# design.net
KiCad netlist of a schematic drawn in Altium Designer
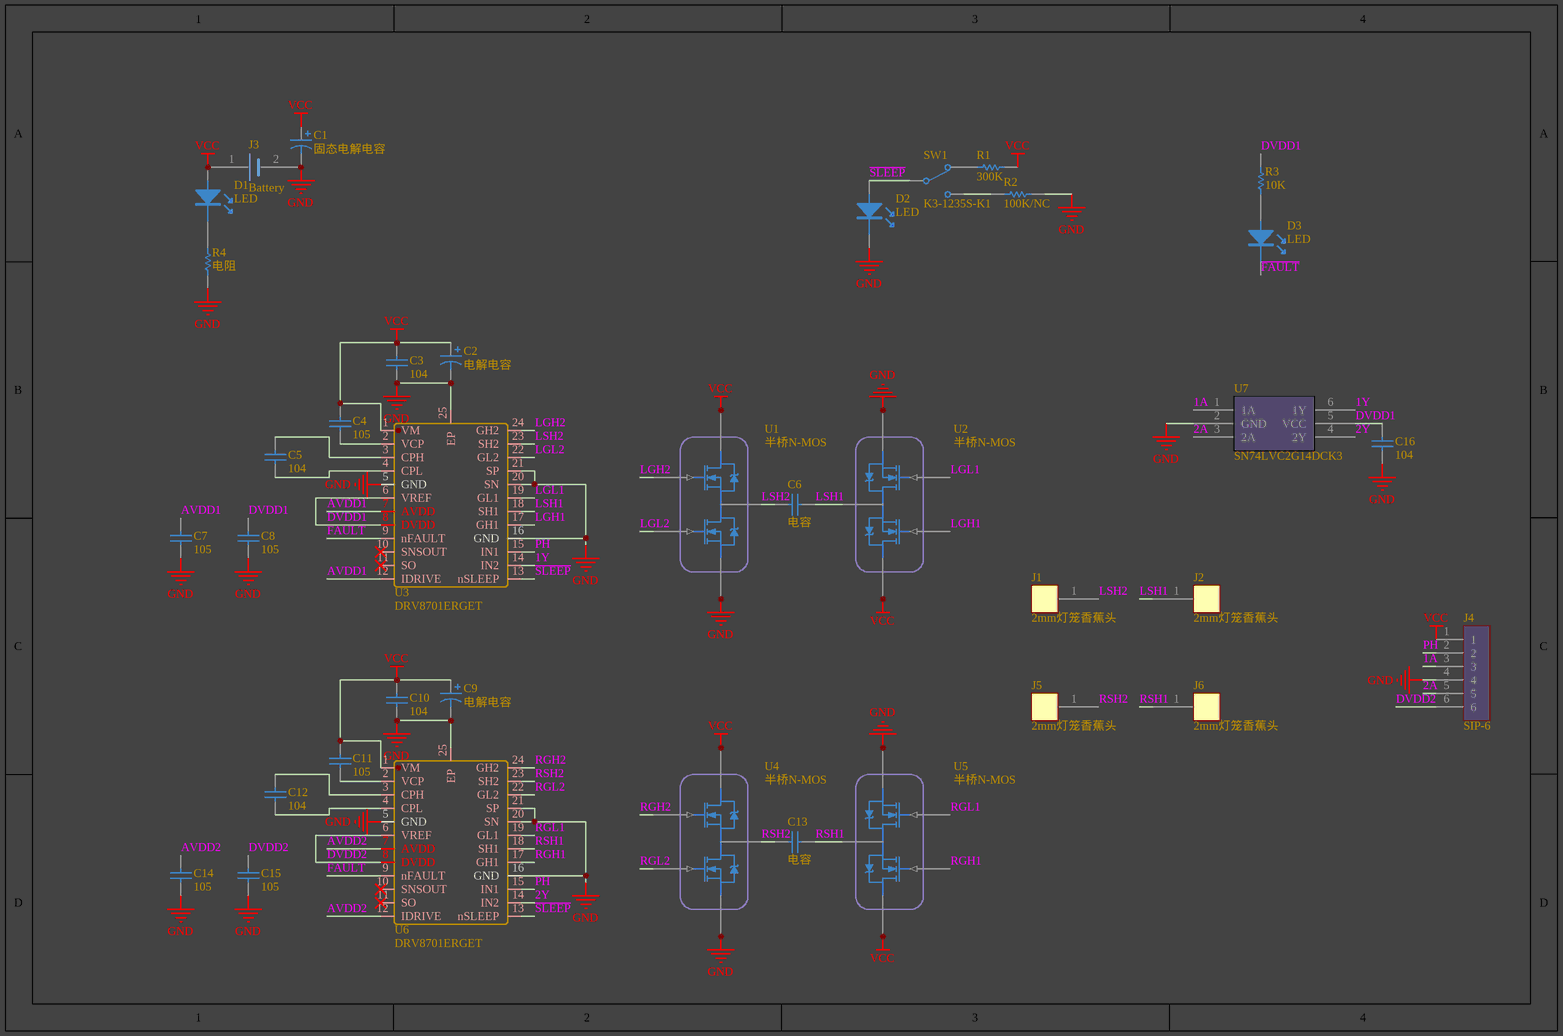
[diagram p0: 原理图.SchDoc]

(export (version "E")
  (design (tool "Eeschema 10.0.6"))
  (components
    (comp (ref "C1")
      (value "固态电解电容")
      (footprint "贴片电解 10*10.5")
      (description "Polarized Capacitor (Axial)")
      (fields (field (name "PUBLISHER") "Altium Limited"))
      (libsource (lib "iMag") (part "电解电容"))
    )
    (comp (ref "C2")
      (value "电解电容")
      (footprint "贴片电解 4*5.4")
      (description "Polarized Capacitor (Axial)")
      (fields (field (name "PUBLISHER") "Altium Limited"))
      (libsource (lib "iMag") (part "电解电容"))
    )
    (comp (ref "C3")
      (value "104")
      (footprint "C0402")
      (description "Capacitor")
      (fields (field (name "PUBLISHER") "Altium Limited"))
      (libsource (lib "iMag") (part "电容"))
    )
    (comp (ref "C4")
      (value "105")
      (footprint "C0402")
      (description "Capacitor")
      (fields (field (name "PUBLISHER") "Altium Limited"))
      (libsource (lib "iMag") (part "电容"))
    )
    (comp (ref "C5")
      (value "104")
      (footprint "C0402")
      (description "Capacitor")
      (fields (field (name "PUBLISHER") "Altium Limited"))
      (libsource (lib "iMag") (part "电容"))
    )
    (comp (ref "C6")
      (value "电容")
      (footprint "C0603")
      (description "Capacitor")
      (fields (field (name "PUBLISHER") "Altium Limited"))
      (libsource (lib "iMag") (part "电容"))
    )
    (comp (ref "C7")
      (value "105")
      (footprint "C0402")
      (description "Capacitor")
      (fields (field (name "PUBLISHER") "Altium Limited"))
      (libsource (lib "iMag") (part "电容"))
    )
    (comp (ref "C8")
      (value "105")
      (footprint "C0402")
      (description "Capacitor")
      (fields (field (name "PUBLISHER") "Altium Limited"))
      (libsource (lib "iMag") (part "电容"))
    )
    (comp (ref "C9")
      (value "电解电容")
      (footprint "贴片电解 4*5.4")
      (description "Polarized Capacitor (Axial)")
      (fields (field (name "PUBLISHER") "Altium Limited"))
      (libsource (lib "iMag") (part "电解电容"))
    )
    (comp (ref "C10")
      (value "104")
      (footprint "C0402")
      (description "Capacitor")
      (fields (field (name "PUBLISHER") "Altium Limited"))
      (libsource (lib "iMag") (part "电容"))
    )
    (comp (ref "C11")
      (value "105")
      (footprint "C0402")
      (description "Capacitor")
      (fields (field (name "PUBLISHER") "Altium Limited"))
      (libsource (lib "iMag") (part "电容"))
    )
    (comp (ref "C12")
      (value "104")
      (footprint "C0402")
      (description "Capacitor")
      (fields (field (name "PUBLISHER") "Altium Limited"))
      (libsource (lib "iMag") (part "电容"))
    )
    (comp (ref "C13")
      (value "电容")
      (footprint "C0603")
      (description "Capacitor")
      (fields (field (name "PUBLISHER") "Altium Limited"))
      (libsource (lib "iMag") (part "电容"))
    )
    (comp (ref "C14")
      (value "105")
      (footprint "C0402")
      (description "Capacitor")
      (fields (field (name "PUBLISHER") "Altium Limited"))
      (libsource (lib "iMag") (part "电容"))
    )
    (comp (ref "C15")
      (value "105")
      (footprint "C0402")
      (description "Capacitor")
      (fields (field (name "PUBLISHER") "Altium Limited"))
      (libsource (lib "iMag") (part "电容"))
    )
    (comp (ref "C16")
      (value "104")
      (footprint "C0402")
      (description "Capacitor")
      (fields (field (name "PUBLISHER") "Altium Limited"))
      (libsource (lib "iMag") (part "电容"))
    )
    (comp (ref "D1") (value "LED") (footprint "LED 0603B") (libsource (lib "iMag") (part "LED")))
    (comp (ref "D2") (value "LED") (footprint "LED 0603G") (libsource (lib "iMag") (part "LED")))
    (comp (ref "D3") (value "LED") (footprint "LED 0603R") (libsource (lib "iMag") (part "LED")))
    (comp (ref "J1") (value "2mm灯笼香蕉头") (footprint "MOTOR") (libsource (lib "") (part "2mm灯笼香蕉头_1")))
    (comp (ref "J2") (value "2mm灯笼香蕉头") (footprint "MOTOR") (libsource (lib "iMag") (part "2mm灯笼香蕉头")))
    (comp (ref "J3") (value "Battery") (footprint "T插") (libsource (lib "iMag") (part "Battery")))
    (comp (ref "J4") (value "SIP-6") (footprint "PH2.0-6P") (libsource (lib "iMag") (part "SIP-6")))
    (comp (ref "J5") (value "2mm灯笼香蕉头") (footprint "MOTOR") (libsource (lib "") (part "2mm灯笼香蕉头_1")))
    (comp (ref "J6") (value "2mm灯笼香蕉头") (footprint "MOTOR") (libsource (lib "iMag") (part "2mm灯笼香蕉头")))
    (comp (ref "R1")
      (value "300K")
      (footprint "R0402")
      (description "Resistor")
      (fields (field (name "PUBLISHER") "Altium Limited"))
      (libsource (lib "iMag") (part "电阻"))
    )
    (comp (ref "R2")
      (value "100K/NC")
      (footprint "R0402")
      (description "Resistor")
      (fields (field (name "PUBLISHER") "Altium Limited"))
      (libsource (lib "iMag") (part "电阻"))
    )
    (comp (ref "R3")
      (value "10K")
      (footprint "R0402")
      (description "Resistor")
      (fields (field (name "PUBLISHER") "Altium Limited"))
      (libsource (lib "iMag") (part "电阻"))
    )
    (comp (ref "R4")
      (value "电阻")
      (footprint "R0402")
      (description "Resistor")
      (fields (field (name "PUBLISHER") "Altium Limited"))
      (libsource (lib "iMag") (part "电阻"))
    )
    (comp (ref "SW1")
      (value "K3-1235S-K1")
      (footprint "K3-1235S-K1")
      (description "Switch")
      (libsource (lib "iMag") (part "单刀双掷"))
    )
    (comp (ref "U1") (value "半桥N-MOS") (footprint "VDFN8") (libsource (lib "iMag") (part "半桥N-MOS")))
    (comp (ref "U2") (value "半桥N-MOS") (footprint "VDFN8") (libsource (lib "iMag") (part "半桥N-MOS")))
    (comp (ref "U3")
      (value "DRV8701ERGET")
      (footprint "VQFN-24_24PIN-L4.00-W4.00-PITCH0.50-EP-TL")
      (description "H桥驱动")
      (fields (field (name "BOM_SUPPLIER PART") "C132049") (field (name "CONTRIBUTOR") "LCSC"))
      (libsource (lib "iMag") (part "DRV8701"))
    )
    (comp (ref "U4") (value "半桥N-MOS") (footprint "VDFN8") (libsource (lib "iMag") (part "半桥N-MOS")))
    (comp (ref "U5") (value "半桥N-MOS") (footprint "VDFN8") (libsource (lib "iMag") (part "半桥N-MOS")))
    (comp (ref "U6")
      (value "DRV8701ERGET")
      (footprint "VQFN-24_24PIN-L4.00-W4.00-PITCH0.50-EP-TL")
      (description "H桥驱动")
      (fields (field (name "BOM_SUPPLIER PART") "C132049") (field (name "CONTRIBUTOR") "LCSC"))
      (libsource (lib "iMag") (part "DRV8701"))
    )
    (comp (ref "U7")
      (value "SN74LVC2G14DCK3")
      (footprint "SC70")
      (description "门级和反向器")
      (fields (field (name "COPYRIGHT") "Copyright (C) 2018 Accelerated Designs. All rights reserved"))
      (libsource (lib "iMag") (part "SN74LVC2G14DCK3"))
    )
  )
  (nets
    (net (code "1") (name "/1A") (class "Default")
      (node (ref "J4") (pin "3") (pinfunction "3_3") (pintype "passive"))
      (node (ref "U7") (pin "1") (pinfunction "1A_1") (pintype "passive"))
    )
    (net (code "2") (name "/1Y") (class "Default")
      (node (ref "U3") (pin "14") (pinfunction "IN2_14") (pintype "passive"))
      (node (ref "U7") (pin "6") (pinfunction "1Y_6") (pintype "passive"))
    )
    (net (code "3") (name "/2A") (class "Default")
      (node (ref "J4") (pin "5") (pinfunction "5_5") (pintype "passive"))
      (node (ref "U7") (pin "3") (pinfunction "2A_3") (pintype "passive"))
    )
    (net (code "4") (name "/2Y") (class "Default")
      (node (ref "U6") (pin "14") (pinfunction "IN2_14") (pintype "passive"))
      (node (ref "U7") (pin "4") (pinfunction "2Y_4") (pintype "passive"))
    )
    (net (code "5") (name "/AVDD1") (class "Default")
      (node (ref "C7") (pin "2") (pinfunction "2_2") (pintype "passive"))
      (node (ref "U3") (pin "12") (pinfunction "IDRIVE_12") (pintype "passive"))
      (node (ref "U3") (pin "7") (pinfunction "AVDD_7") (pintype "passive"))
    )
    (net (code "6") (name "/AVDD2") (class "Default")
      (node (ref "C14") (pin "2") (pinfunction "2_2") (pintype "passive"))
      (node (ref "U6") (pin "12") (pinfunction "IDRIVE_12") (pintype "passive"))
      (node (ref "U6") (pin "7") (pinfunction "AVDD_7") (pintype "passive"))
    )
    (net (code "7") (name "/DVDD1") (class "Default")
      (node (ref "C16") (pin "2") (pinfunction "2_2") (pintype "passive"))
      (node (ref "C8") (pin "2") (pinfunction "2_2") (pintype "passive"))
      (node (ref "R3") (pin "1") (pinfunction "1_1") (pintype "passive"))
      (node (ref "U3") (pin "6") (pinfunction "VREF_6") (pintype "passive"))
      (node (ref "U3") (pin "8") (pinfunction "DVDD_8") (pintype "passive"))
      (node (ref "U7") (pin "5") (pinfunction "VCC_5") (pintype "passive"))
    )
    (net (code "8") (name "/DVDD2") (class "Default")
      (node (ref "C15") (pin "2") (pinfunction "2_2") (pintype "passive"))
      (node (ref "J4") (pin "6") (pinfunction "6_6") (pintype "passive"))
      (node (ref "U6") (pin "6") (pinfunction "VREF_6") (pintype "passive"))
      (node (ref "U6") (pin "8") (pinfunction "DVDD_8") (pintype "passive"))
    )
    (net (code "9") (name "/FAULT") (class "Default")
      (node (ref "D3") (pin "K") (pinfunction "2_K") (pintype "passive"))
      (node (ref "U3") (pin "9") (pinfunction "nFAULT_9") (pintype "passive"))
      (node (ref "U6") (pin "9") (pinfunction "nFAULT_9") (pintype "passive"))
    )
    (net (code "10") (name "/LGH1") (class "Default")
      (node (ref "U2") (pin "1") (pinfunction "GH_1") (pintype "input"))
      (node (ref "U3") (pin "17") (pinfunction "GH1_17") (pintype "passive"))
    )
    (net (code "11") (name "/LGH2") (class "Default")
      (node (ref "U1") (pin "1") (pinfunction "GH_1") (pintype "input"))
      (node (ref "U3") (pin "24") (pinfunction "GH2_24") (pintype "passive"))
    )
    (net (code "12") (name "/LGL1") (class "Default")
      (node (ref "U2") (pin "8") (pinfunction "GL_8") (pintype "input"))
      (node (ref "U3") (pin "19") (pinfunction "GL1_19") (pintype "passive"))
    )
    (net (code "13") (name "/LGL2") (class "Default")
      (node (ref "U1") (pin "8") (pinfunction "GL_8") (pintype "input"))
      (node (ref "U3") (pin "22") (pinfunction "GL2_22") (pintype "passive"))
    )
    (net (code "14") (name "/LSH1") (class "Default")
      (node (ref "C6") (pin "2") (pinfunction "2_2") (pintype "passive"))
      (node (ref "J2") (pin "1") (pinfunction "0_1") (pintype "passive"))
      (node (ref "U2") (pin "9") (pinfunction "9_9") (pintype "passive"))
      (node (ref "U3") (pin "18") (pinfunction "SH1_18") (pintype "passive"))
    )
    (net (code "15") (name "/LSH2") (class "Default")
      (node (ref "C6") (pin "1") (pinfunction "1_1") (pintype "passive"))
      (node (ref "J1") (pin "1") (pinfunction "0_1") (pintype "passive"))
      (node (ref "U1") (pin "9") (pinfunction "9_9") (pintype "passive"))
      (node (ref "U3") (pin "23") (pinfunction "SH2_23") (pintype "passive"))
    )
    (net (code "16") (name "/PH") (class "Default")
      (node (ref "J4") (pin "2") (pinfunction "2_2") (pintype "passive"))
      (node (ref "U3") (pin "15") (pinfunction "IN1_15") (pintype "passive"))
      (node (ref "U6") (pin "15") (pinfunction "IN1_15") (pintype "passive"))
    )
    (net (code "17") (name "/RGH1") (class "Default")
      (node (ref "U5") (pin "1") (pinfunction "GH_1") (pintype "input"))
      (node (ref "U6") (pin "17") (pinfunction "GH1_17") (pintype "passive"))
    )
    (net (code "18") (name "/RGH2") (class "Default")
      (node (ref "U4") (pin "1") (pinfunction "GH_1") (pintype "input"))
      (node (ref "U6") (pin "24") (pinfunction "GH2_24") (pintype "passive"))
    )
    (net (code "19") (name "/RGL1") (class "Default")
      (node (ref "U5") (pin "8") (pinfunction "GL_8") (pintype "input"))
      (node (ref "U6") (pin "19") (pinfunction "GL1_19") (pintype "passive"))
    )
    (net (code "20") (name "/RGL2") (class "Default")
      (node (ref "U4") (pin "8") (pinfunction "GL_8") (pintype "input"))
      (node (ref "U6") (pin "22") (pinfunction "GL2_22") (pintype "passive"))
    )
    (net (code "21") (name "/RSH1") (class "Default")
      (node (ref "C13") (pin "2") (pinfunction "2_2") (pintype "passive"))
      (node (ref "J6") (pin "1") (pinfunction "0_1") (pintype "passive"))
      (node (ref "U5") (pin "9") (pinfunction "9_9") (pintype "passive"))
      (node (ref "U6") (pin "18") (pinfunction "SH1_18") (pintype "passive"))
    )
    (net (code "22") (name "/RSH2") (class "Default")
      (node (ref "C13") (pin "1") (pinfunction "1_1") (pintype "passive"))
      (node (ref "J5") (pin "1") (pinfunction "0_1") (pintype "passive"))
      (node (ref "U4") (pin "9") (pinfunction "9_9") (pintype "passive"))
      (node (ref "U6") (pin "23") (pinfunction "SH2_23") (pintype "passive"))
    )
    (net (code "23") (name "/SLEEP") (class "Default")
      (node (ref "D2") (pin "A") (pinfunction "1_A") (pintype "passive"))
      (node (ref "SW1") (pin "2") (pinfunction "2_2") (pintype "passive"))
      (node (ref "U3") (pin "13") (pinfunction "nSLEEP_13") (pintype "passive"))
      (node (ref "U6") (pin "13") (pinfunction "nSLEEP_13") (pintype "passive"))
    )
    (net (code "24") (name "GND") (class "Default")
      (node (ref "C1") (pin "2") (pinfunction "2_2") (pintype "passive"))
      (node (ref "C10") (pin "1") (pinfunction "1_1") (pintype "passive"))
      (node (ref "C14") (pin "1") (pinfunction "1_1") (pintype "passive"))
      (node (ref "C15") (pin "1") (pinfunction "1_1") (pintype "passive"))
      (node (ref "C16") (pin "1") (pinfunction "1_1") (pintype "passive"))
      (node (ref "C2") (pin "2") (pinfunction "2_2") (pintype "passive"))
      (node (ref "C3") (pin "1") (pinfunction "1_1") (pintype "passive"))
      (node (ref "C7") (pin "1") (pinfunction "1_1") (pintype "passive"))
      (node (ref "C8") (pin "1") (pinfunction "1_1") (pintype "passive"))
      (node (ref "C9") (pin "2") (pinfunction "2_2") (pintype "passive"))
      (node (ref "D2") (pin "K") (pinfunction "2_K") (pintype "passive"))
      (node (ref "J3") (pin "2") (pinfunction "-_2") (pintype "passive"))
      (node (ref "J4") (pin "4") (pinfunction "4_4") (pintype "passive"))
      (node (ref "R2") (pin "1") (pinfunction "1_1") (pintype "passive"))
      (node (ref "R4") (pin "1") (pinfunction "1_1") (pintype "passive"))
      (node (ref "U1") (pin "5") (pinfunction "SL_5") (pintype "passive"))
      (node (ref "U1") (pin "6") (pinfunction "SL_6") (pintype "passive"))
      (node (ref "U1") (pin "7") (pinfunction "S_7") (pintype "passive"))
      (node (ref "U2") (pin "5") (pinfunction "SL_5") (pintype "passive"))
      (node (ref "U2") (pin "6") (pinfunction "SL_6") (pintype "passive"))
      (node (ref "U2") (pin "7") (pinfunction "S_7") (pintype "passive"))
      (node (ref "U3") (pin "16") (pinfunction "GND_16") (pintype "passive"))
      (node (ref "U3") (pin "20") (pinfunction "SN_20") (pintype "passive"))
      (node (ref "U3") (pin "21") (pinfunction "SP_21") (pintype "passive"))
      (node (ref "U3") (pin "25") (pinfunction "EP_25") (pintype "passive"))
      (node (ref "U3") (pin "5") (pinfunction "GND_5") (pintype "passive"))
      (node (ref "U4") (pin "5") (pinfunction "SL_5") (pintype "passive"))
      (node (ref "U4") (pin "6") (pinfunction "SL_6") (pintype "passive"))
      (node (ref "U4") (pin "7") (pinfunction "S_7") (pintype "passive"))
      (node (ref "U5") (pin "5") (pinfunction "SL_5") (pintype "passive"))
      (node (ref "U5") (pin "6") (pinfunction "SL_6") (pintype "passive"))
      (node (ref "U5") (pin "7") (pinfunction "S_7") (pintype "passive"))
      (node (ref "U6") (pin "16") (pinfunction "GND_16") (pintype "passive"))
      (node (ref "U6") (pin "20") (pinfunction "SN_20") (pintype "passive"))
      (node (ref "U6") (pin "21") (pinfunction "SP_21") (pintype "passive"))
      (node (ref "U6") (pin "25") (pinfunction "EP_25") (pintype "passive"))
      (node (ref "U6") (pin "5") (pinfunction "GND_5") (pintype "passive"))
      (node (ref "U7") (pin "2") (pinfunction "GND_2") (pintype "passive"))
    )
    (net (code "25") (name "Net-(D1-2)") (class "Default")
      (node (ref "D1") (pin "K") (pinfunction "2_K") (pintype "passive"))
      (node (ref "R4") (pin "2") (pinfunction "2_2") (pintype "passive"))
    )
    (net (code "26") (name "Net-(D3-1)") (class "Default")
      (node (ref "D3") (pin "A") (pinfunction "1_A") (pintype "passive"))
      (node (ref "R3") (pin "2") (pinfunction "2_2") (pintype "passive"))
    )
    (net (code "27") (name "Net-(R1-Pad2)") (class "Default")
      (node (ref "R1") (pin "2") (pinfunction "2_2") (pintype "passive"))
      (node (ref "SW1") (pin "1") (pinfunction "1_1") (pintype "passive"))
    )
    (net (code "28") (name "Net-(R2-Pad2)") (class "Default")
      (node (ref "R2") (pin "2") (pinfunction "2_2") (pintype "passive"))
      (node (ref "SW1") (pin "3") (pinfunction "3_3") (pintype "passive"))
    )
    (net (code "29") (name "Net-(U3-CPH)") (class "Default")
      (node (ref "C5") (pin "2") (pinfunction "2_2") (pintype "passive"))
      (node (ref "U3") (pin "3") (pinfunction "CPH_3") (pintype "passive"))
    )
    (net (code "30") (name "Net-(U3-CPL)") (class "Default")
      (node (ref "C5") (pin "1") (pinfunction "1_1") (pintype "passive"))
      (node (ref "U3") (pin "4") (pinfunction "CPL_4") (pintype "passive"))
    )
    (net (code "31") (name "Net-(U3-VCP)") (class "Default")
      (node (ref "C4") (pin "1") (pinfunction "1_1") (pintype "passive"))
      (node (ref "U3") (pin "2") (pinfunction "VCP_2") (pintype "passive"))
    )
    (net (code "32") (name "Net-(U6-CPH)") (class "Default")
      (node (ref "C12") (pin "2") (pinfunction "2_2") (pintype "passive"))
      (node (ref "U6") (pin "3") (pinfunction "CPH_3") (pintype "passive"))
    )
    (net (code "33") (name "Net-(U6-CPL)") (class "Default")
      (node (ref "C12") (pin "1") (pinfunction "1_1") (pintype "passive"))
      (node (ref "U6") (pin "4") (pinfunction "CPL_4") (pintype "passive"))
    )
    (net (code "34") (name "Net-(U6-VCP)") (class "Default")
      (node (ref "C11") (pin "1") (pinfunction "1_1") (pintype "passive"))
      (node (ref "U6") (pin "2") (pinfunction "VCP_2") (pintype "passive"))
    )
    (net (code "35") (name "VCC") (class "Default")
      (node (ref "C1") (pin "1") (pinfunction "1_1") (pintype "passive"))
      (node (ref "C10") (pin "2") (pinfunction "2_2") (pintype "passive"))
      (node (ref "C11") (pin "2") (pinfunction "2_2") (pintype "passive"))
      (node (ref "C2") (pin "1") (pinfunction "1_1") (pintype "passive"))
      (node (ref "C3") (pin "2") (pinfunction "2_2") (pintype "passive"))
      (node (ref "C4") (pin "2") (pinfunction "2_2") (pintype "passive"))
      (node (ref "C9") (pin "1") (pinfunction "1_1") (pintype "passive"))
      (node (ref "D1") (pin "A") (pinfunction "1_A") (pintype "passive"))
      (node (ref "J3") (pin "1") (pinfunction "+_1") (pintype "passive"))
      (node (ref "J4") (pin "1") (pinfunction "1_1") (pintype "passive"))
      (node (ref "R1") (pin "1") (pinfunction "1_1") (pintype "passive"))
      (node (ref "U1") (pin "10") (pinfunction "D_10") (pintype "passive"))
      (node (ref "U1") (pin "2") (pinfunction "D_2") (pintype "passive"))
      (node (ref "U1") (pin "3") (pinfunction "D_3") (pintype "passive"))
      (node (ref "U1") (pin "4") (pinfunction "D_4") (pintype "passive"))
      (node (ref "U2") (pin "10") (pinfunction "D_10") (pintype "passive"))
      (node (ref "U2") (pin "2") (pinfunction "D_2") (pintype "passive"))
      (node (ref "U2") (pin "3") (pinfunction "D_3") (pintype "passive"))
      (node (ref "U2") (pin "4") (pinfunction "D_4") (pintype "passive"))
      (node (ref "U3") (pin "1") (pinfunction "VM_1") (pintype "passive"))
      (node (ref "U4") (pin "10") (pinfunction "D_10") (pintype "passive"))
      (node (ref "U4") (pin "2") (pinfunction "D_2") (pintype "passive"))
      (node (ref "U4") (pin "3") (pinfunction "D_3") (pintype "passive"))
      (node (ref "U4") (pin "4") (pinfunction "D_4") (pintype "passive"))
      (node (ref "U5") (pin "10") (pinfunction "D_10") (pintype "passive"))
      (node (ref "U5") (pin "2") (pinfunction "D_2") (pintype "passive"))
      (node (ref "U5") (pin "3") (pinfunction "D_3") (pintype "passive"))
      (node (ref "U5") (pin "4") (pinfunction "D_4") (pintype "passive"))
      (node (ref "U6") (pin "1") (pinfunction "VM_1") (pintype "passive"))
    )
    (net (code "36") (name "unconnected-(U3-SNSOUT-Pad10)") (class "Default")
      (node (ref "U3") (pin "10") (pinfunction "SNSOUT_10") (pintype "passive+no_connect"))
    )
    (net (code "37") (name "unconnected-(U3-SO-Pad11)") (class "Default")
      (node (ref "U3") (pin "11") (pinfunction "SO_11") (pintype "passive+no_connect"))
    )
    (net (code "38") (name "unconnected-(U6-SNSOUT-Pad10)") (class "Default")
      (node (ref "U6") (pin "10") (pinfunction "SNSOUT_10") (pintype "passive+no_connect"))
    )
    (net (code "39") (name "unconnected-(U6-SO-Pad11)") (class "Default")
      (node (ref "U6") (pin "11") (pinfunction "SO_11") (pintype "passive+no_connect"))
    )
  )
)
